# Sensor_module.net
KiCad netlist of a schematic drawn in Altium Designer
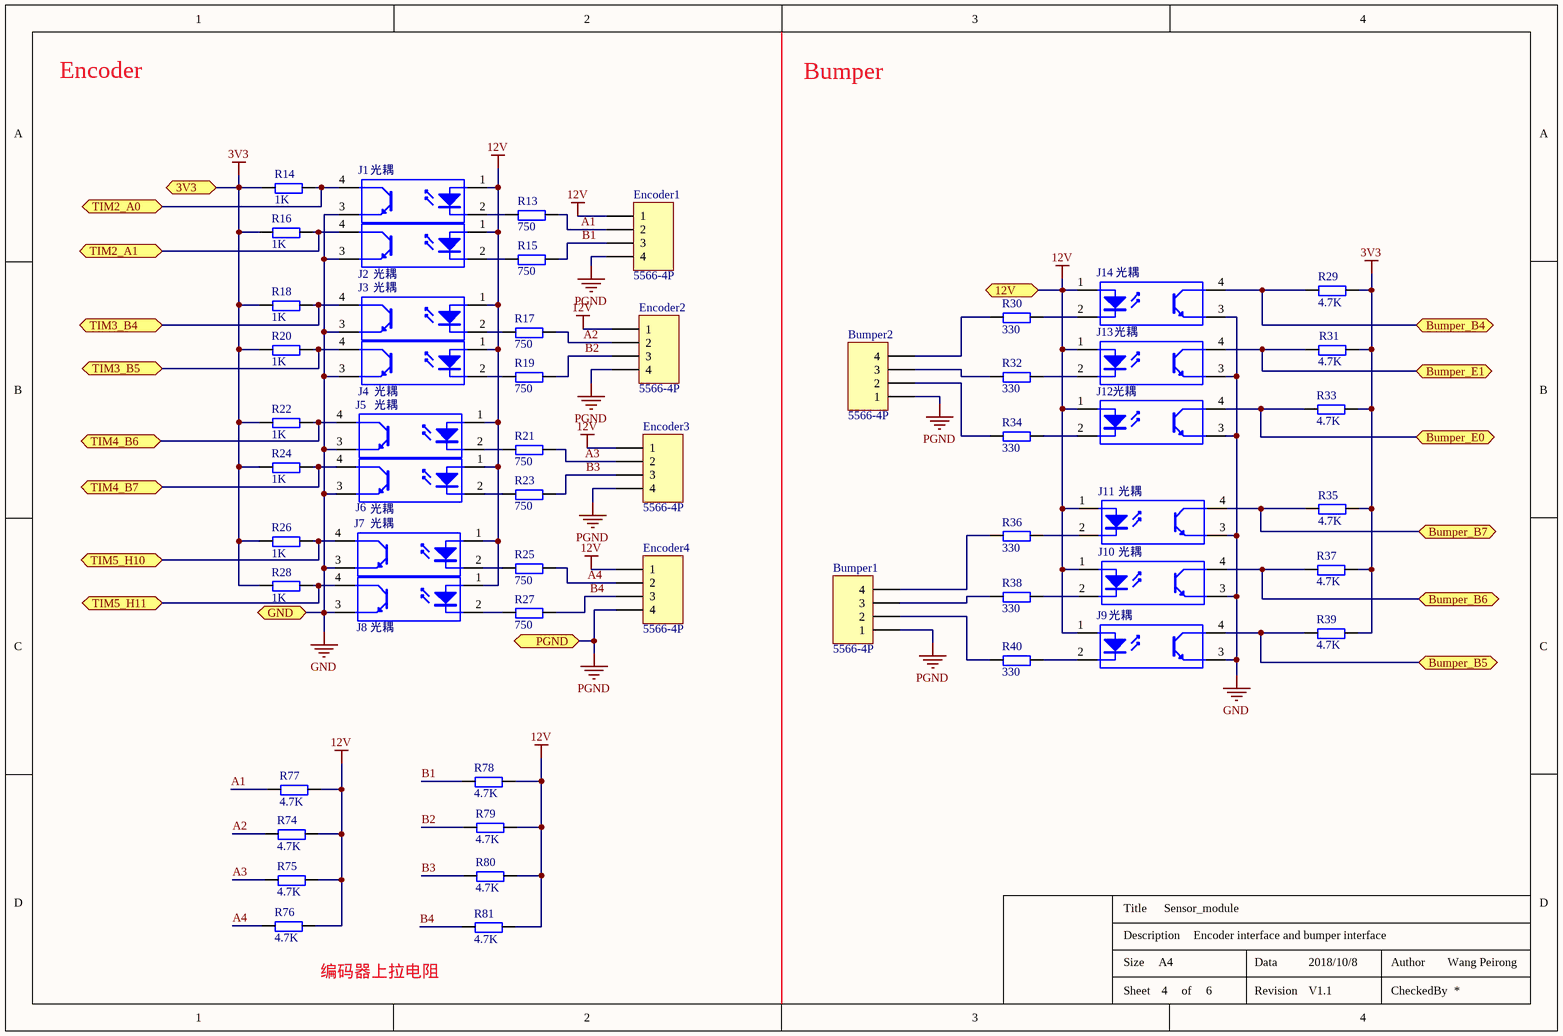
[diagram p0: Sensor_module.SchDoc]

(export (version "E")
  (design (tool "Eeschema 10.0.6"))
  (components
    (comp (ref "Bumper1")
      (value "5566-4P")
      (footprint "5566-4P")
      (description "Header, 4-Pin")
      (fields (field (name "PUBLISHER") "Altium Limited"))
      (libsource (lib "") (part "Header 4_1"))
    )
    (comp (ref "Bumper2")
      (value "5566-4P")
      (footprint "5566-4P")
      (description "Header, 4-Pin")
      (fields (field (name "PUBLISHER") "Altium Limited"))
      (libsource (lib "") (part "Header 4_1"))
    )
    (comp (ref "Encoder1")
      (value "5566-4P")
      (footprint "5566-4P")
      (description "Header, 4-Pin")
      (fields (field (name "PUBLISHER") "Altium Limited"))
      (libsource (lib "接插件集成库") (part "Header 4"))
    )
    (comp (ref "Encoder2")
      (value "5566-4P")
      (footprint "5566-4P")
      (description "Header, 4-Pin")
      (fields (field (name "PUBLISHER") "Altium Limited"))
      (libsource (lib "接插件集成库") (part "Header 4"))
    )
    (comp (ref "Encoder3")
      (value "5566-4P")
      (footprint "5566-4P")
      (description "Header, 4-Pin")
      (fields (field (name "PUBLISHER") "Altium Limited"))
      (libsource (lib "接插件集成库") (part "Header 4"))
    )
    (comp (ref "Encoder4")
      (value "5566-4P")
      (footprint "5566-4P")
      (description "Header, 4-Pin")
      (fields (field (name "PUBLISHER") "Altium Limited"))
      (libsource (lib "接插件集成库") (part "Header 4"))
    )
    (comp (ref "J1")
      (value "光耦")
      (footprint "SOP127P710X350-4N")
      (fields (field (name "PUBLISHER") "Altium Limited"))
      (libsource (lib "常用元件集成库") (part "光耦"))
    )
    (comp (ref "J2")
      (value "光耦")
      (footprint "SOP127P710X350-4N")
      (fields (field (name "PUBLISHER") "Altium Limited"))
      (libsource (lib "常用元件集成库") (part "光耦"))
    )
    (comp (ref "J3")
      (value "光耦")
      (footprint "SOP127P710X350-4N")
      (fields (field (name "PUBLISHER") "Altium Limited"))
      (libsource (lib "常用元件集成库") (part "光耦"))
    )
    (comp (ref "J4")
      (value "光耦")
      (footprint "SOP127P710X350-4N")
      (fields (field (name "PUBLISHER") "Altium Limited"))
      (libsource (lib "常用元件集成库") (part "光耦"))
    )
    (comp (ref "J5")
      (value "光耦")
      (footprint "SOP127P710X350-4N")
      (fields (field (name "PUBLISHER") "Altium Limited"))
      (libsource (lib "常用元件集成库") (part "光耦"))
    )
    (comp (ref "J6")
      (value "光耦")
      (footprint "SOP127P710X350-4N")
      (fields (field (name "PUBLISHER") "Altium Limited"))
      (libsource (lib "常用元件集成库") (part "光耦"))
    )
    (comp (ref "J7")
      (value "光耦")
      (footprint "SOP127P710X350-4N")
      (fields (field (name "PUBLISHER") "Altium Limited"))
      (libsource (lib "常用元件集成库") (part "光耦"))
    )
    (comp (ref "J8")
      (value "光耦")
      (footprint "SOP127P710X350-4N")
      (fields (field (name "PUBLISHER") "Altium Limited"))
      (libsource (lib "常用元件集成库") (part "光耦"))
    )
    (comp (ref "J9")
      (value "光耦")
      (footprint "SOP127P710X350-4N")
      (fields (field (name "PUBLISHER") "Altium Limited"))
      (libsource (lib "常用元件集成库") (part "光耦"))
    )
    (comp (ref "J10")
      (value "光耦")
      (footprint "SOP127P710X350-4N")
      (fields (field (name "PUBLISHER") "Altium Limited"))
      (libsource (lib "常用元件集成库") (part "光耦"))
    )
    (comp (ref "J11")
      (value "光耦")
      (footprint "SOP127P710X350-4N")
      (fields (field (name "PUBLISHER") "Altium Limited"))
      (libsource (lib "常用元件集成库") (part "光耦"))
    )
    (comp (ref "J12")
      (value "光耦")
      (footprint "SOP127P710X350-4N")
      (fields (field (name "PUBLISHER") "Altium Limited"))
      (libsource (lib "常用元件集成库") (part "光耦"))
    )
    (comp (ref "J13")
      (value "光耦")
      (footprint "SOP127P710X350-4N")
      (fields (field (name "PUBLISHER") "Altium Limited"))
      (libsource (lib "常用元件集成库") (part "光耦"))
    )
    (comp (ref "J14")
      (value "光耦")
      (footprint "SOP127P710X350-4N")
      (fields (field (name "PUBLISHER") "Altium Limited"))
      (libsource (lib "常用元件集成库") (part "光耦"))
    )
    (comp (ref "R13") (value "750") (footprint "0603P") (libsource (lib "STM32F429核心板封装库") (part "R")))
    (comp (ref "R14") (value "1K") (footprint "0603P") (libsource (lib "STM32F429核心板封装库") (part "R")))
    (comp (ref "R15") (value "750") (footprint "0603P") (libsource (lib "阿波罗STM32F4&F7底板封装库") (part "R")))
    (comp (ref "R16") (value "1K") (footprint "0603P") (libsource (lib "阿波罗STM32F4&F7底板封装库") (part "R")))
    (comp (ref "R17") (value "750") (footprint "0603P") (libsource (lib "阿波罗STM32F4&F7底板封装库") (part "R")))
    (comp (ref "R18") (value "1K") (footprint "0603P") (libsource (lib "阿波罗STM32F4&F7底板封装库") (part "R")))
    (comp (ref "R19") (value "750") (footprint "0603P") (libsource (lib "阿波罗STM32F4&F7底板封装库") (part "R")))
    (comp (ref "R20") (value "1K") (footprint "0603P") (libsource (lib "阿波罗STM32F4&F7底板封装库") (part "R")))
    (comp (ref "R21") (value "750") (footprint "0603P") (libsource (lib "阿波罗STM32F4&F7底板封装库") (part "R")))
    (comp (ref "R22") (value "1K") (footprint "0603P") (libsource (lib "阿波罗STM32F4&F7底板封装库") (part "R")))
    (comp (ref "R23") (value "750") (footprint "0603P") (libsource (lib "阿波罗STM32F4&F7底板封装库") (part "R")))
    (comp (ref "R24") (value "1K") (footprint "0603P") (libsource (lib "阿波罗STM32F4&F7底板封装库") (part "R")))
    (comp (ref "R25") (value "750") (footprint "0603P") (libsource (lib "阿波罗STM32F4&F7底板封装库") (part "R")))
    (comp (ref "R26") (value "1K") (footprint "0603P") (libsource (lib "阿波罗STM32F4&F7底板封装库") (part "R")))
    (comp (ref "R27") (value "750") (footprint "0603P") (libsource (lib "阿波罗STM32F4&F7底板封装库") (part "R")))
    (comp (ref "R28") (value "1K") (footprint "0603P") (libsource (lib "阿波罗STM32F4&F7底板封装库") (part "R")))
    (comp (ref "R29") (value "4.7K") (footprint "0603P") (libsource (lib "阿波罗STM32F4&F7底板封装库") (part "R")))
    (comp (ref "R30") (value "330") (footprint "0603P") (libsource (lib "阿波罗STM32F4&F7底板封装库") (part "R")))
    (comp (ref "R31") (value "4.7K") (footprint "0603P") (libsource (lib "阿波罗STM32F4&F7底板封装库") (part "R")))
    (comp (ref "R32") (value "330") (footprint "0603P") (libsource (lib "阿波罗STM32F4&F7底板封装库") (part "R")))
    (comp (ref "R33") (value "4.7K") (footprint "0603P") (libsource (lib "阿波罗STM32F4&F7底板封装库") (part "R")))
    (comp (ref "R34") (value "330") (footprint "0603P") (libsource (lib "阿波罗STM32F4&F7底板封装库") (part "R")))
    (comp (ref "R35") (value "4.7K") (footprint "0603P") (libsource (lib "阿波罗STM32F4&F7底板封装库") (part "R")))
    (comp (ref "R36") (value "330") (footprint "0603P") (libsource (lib "阿波罗STM32F4&F7底板封装库") (part "R")))
    (comp (ref "R37") (value "4.7K") (footprint "0603P") (libsource (lib "阿波罗STM32F4&F7底板封装库") (part "R")))
    (comp (ref "R38") (value "330") (footprint "0603P") (libsource (lib "阿波罗STM32F4&F7底板封装库") (part "R")))
    (comp (ref "R39") (value "4.7K") (footprint "0603P") (libsource (lib "阿波罗STM32F4&F7底板封装库") (part "R")))
    (comp (ref "R40") (value "330") (footprint "0603P") (libsource (lib "阿波罗STM32F4&F7底板封装库") (part "R")))
    (comp (ref "R74") (value "4.7K") (footprint "0603P") (libsource (lib "阿波罗STM32F4&F7底板封装库") (part "R")))
    (comp (ref "R75") (value "4.7K") (footprint "0603P") (libsource (lib "阿波罗STM32F4&F7底板封装库") (part "R")))
    (comp (ref "R76") (value "4.7K") (footprint "0603P") (libsource (lib "阿波罗STM32F4&F7底板封装库") (part "R")))
    (comp (ref "R77") (value "4.7K") (footprint "0603P") (libsource (lib "阿波罗STM32F4&F7底板封装库") (part "R")))
    (comp (ref "R78") (value "4.7K") (footprint "0603P") (libsource (lib "阿波罗STM32F4&F7底板封装库") (part "R")))
    (comp (ref "R79") (value "4.7K") (footprint "0603P") (libsource (lib "阿波罗STM32F4&F7底板封装库") (part "R")))
    (comp (ref "R80") (value "4.7K") (footprint "0603P") (libsource (lib "阿波罗STM32F4&F7底板封装库") (part "R")))
    (comp (ref "R81") (value "4.7K") (footprint "0603P") (libsource (lib "阿波罗STM32F4&F7底板封装库") (part "R")))
  )
  (nets
    (net (code "1") (name "/A1") (class "Default")
      (node (ref "Encoder1") (pin "2") (pinfunction "2_2") (pintype "passive"))
      (node (ref "R13") (pin "1") (pintype "passive"))
      (node (ref "R77") (pin "1") (pintype "passive"))
    )
    (net (code "2") (name "/A2") (class "Default")
      (node (ref "Encoder2") (pin "2") (pinfunction "2_2") (pintype "passive"))
      (node (ref "R17") (pin "1") (pintype "passive"))
      (node (ref "R74") (pin "1") (pintype "passive"))
    )
    (net (code "3") (name "/A3") (class "Default")
      (node (ref "Encoder3") (pin "2") (pinfunction "2_2") (pintype "passive"))
      (node (ref "R21") (pin "1") (pintype "passive"))
      (node (ref "R75") (pin "1") (pintype "passive"))
    )
    (net (code "4") (name "/A4") (class "Default")
      (node (ref "Encoder4") (pin "2") (pinfunction "2_2") (pintype "passive"))
      (node (ref "R25") (pin "1") (pintype "passive"))
      (node (ref "R76") (pin "1") (pintype "passive"))
    )
    (net (code "5") (name "/B1") (class "Default")
      (node (ref "Encoder1") (pin "3") (pinfunction "3_3") (pintype "passive"))
      (node (ref "R15") (pin "1") (pintype "passive"))
      (node (ref "R78") (pin "1") (pintype "passive"))
    )
    (net (code "6") (name "/B2") (class "Default")
      (node (ref "Encoder2") (pin "3") (pinfunction "3_3") (pintype "passive"))
      (node (ref "R19") (pin "1") (pintype "passive"))
      (node (ref "R79") (pin "1") (pintype "passive"))
    )
    (net (code "7") (name "/B3") (class "Default")
      (node (ref "Encoder3") (pin "3") (pinfunction "3_3") (pintype "passive"))
      (node (ref "R23") (pin "1") (pintype "passive"))
      (node (ref "R80") (pin "1") (pintype "passive"))
    )
    (net (code "8") (name "/B4") (class "Default")
      (node (ref "Encoder4") (pin "3") (pinfunction "3_3") (pintype "passive"))
      (node (ref "R27") (pin "1") (pintype "passive"))
      (node (ref "R81") (pin "1") (pintype "passive"))
    )
    (net (code "9") (name "/Bumper_B4") (class "Default")
      (node (ref "J14") (pin "4") (pinfunction "C_4") (pintype "passive"))
      (node (ref "R29") (pin "1") (pintype "passive"))
    )
    (net (code "10") (name "/Bumper_B5") (class "Default")
      (node (ref "J9") (pin "4") (pinfunction "C_4") (pintype "passive"))
      (node (ref "R39") (pin "1") (pintype "passive"))
    )
    (net (code "11") (name "/Bumper_B6") (class "Default")
      (node (ref "J10") (pin "4") (pinfunction "C_4") (pintype "passive"))
      (node (ref "R37") (pin "1") (pintype "passive"))
    )
    (net (code "12") (name "/Bumper_B7") (class "Default")
      (node (ref "J11") (pin "4") (pinfunction "C_4") (pintype "passive"))
      (node (ref "R35") (pin "1") (pintype "passive"))
    )
    (net (code "13") (name "/Bumper_E0") (class "Default")
      (node (ref "J12") (pin "4") (pinfunction "C_4") (pintype "passive"))
      (node (ref "R33") (pin "1") (pintype "passive"))
    )
    (net (code "14") (name "/Bumper_E1") (class "Default")
      (node (ref "J13") (pin "4") (pinfunction "C_4") (pintype "passive"))
      (node (ref "R31") (pin "1") (pintype "passive"))
    )
    (net (code "15") (name "/TIM2_A0") (class "Default")
      (node (ref "J1") (pin "4") (pinfunction "C_4") (pintype "passive"))
      (node (ref "R14") (pin "1") (pintype "passive"))
    )
    (net (code "16") (name "/TIM2_A1") (class "Default")
      (node (ref "J2") (pin "4") (pinfunction "C_4") (pintype "passive"))
      (node (ref "R16") (pin "1") (pintype "passive"))
    )
    (net (code "17") (name "/TIM3_B4") (class "Default")
      (node (ref "J3") (pin "4") (pinfunction "C_4") (pintype "passive"))
      (node (ref "R18") (pin "1") (pintype "passive"))
    )
    (net (code "18") (name "/TIM3_B5") (class "Default")
      (node (ref "J4") (pin "4") (pinfunction "C_4") (pintype "passive"))
      (node (ref "R20") (pin "1") (pintype "passive"))
    )
    (net (code "19") (name "/TIM4_B6") (class "Default")
      (node (ref "J5") (pin "4") (pinfunction "C_4") (pintype "passive"))
      (node (ref "R22") (pin "1") (pintype "passive"))
    )
    (net (code "20") (name "/TIM4_B7") (class "Default")
      (node (ref "J6") (pin "4") (pinfunction "C_4") (pintype "passive"))
      (node (ref "R24") (pin "1") (pintype "passive"))
    )
    (net (code "21") (name "/TIM5_H10") (class "Default")
      (node (ref "J7") (pin "4") (pinfunction "C_4") (pintype "passive"))
      (node (ref "R26") (pin "1") (pintype "passive"))
    )
    (net (code "22") (name "/TIM5_H11") (class "Default")
      (node (ref "J8") (pin "4") (pinfunction "C_4") (pintype "passive"))
      (node (ref "R28") (pin "1") (pintype "passive"))
    )
    (net (code "23") (name "3V3") (class "Default")
      (node (ref "R14") (pin "2") (pintype "passive"))
      (node (ref "R16") (pin "2") (pintype "passive"))
      (node (ref "R18") (pin "2") (pintype "passive"))
      (node (ref "R20") (pin "2") (pintype "passive"))
      (node (ref "R22") (pin "2") (pintype "passive"))
      (node (ref "R24") (pin "2") (pintype "passive"))
      (node (ref "R26") (pin "2") (pintype "passive"))
      (node (ref "R28") (pin "2") (pintype "passive"))
      (node (ref "R29") (pin "2") (pintype "passive"))
      (node (ref "R31") (pin "2") (pintype "passive"))
      (node (ref "R33") (pin "2") (pintype "passive"))
      (node (ref "R35") (pin "2") (pintype "passive"))
      (node (ref "R37") (pin "2") (pintype "passive"))
      (node (ref "R39") (pin "2") (pintype "passive"))
    )
    (net (code "24") (name "12V") (class "Default")
      (node (ref "Encoder1") (pin "1") (pinfunction "1_1") (pintype "passive"))
      (node (ref "Encoder2") (pin "1") (pinfunction "1_1") (pintype "passive"))
      (node (ref "Encoder3") (pin "1") (pinfunction "1_1") (pintype "passive"))
      (node (ref "Encoder4") (pin "1") (pinfunction "1_1") (pintype "passive"))
      (node (ref "J1") (pin "1") (pinfunction "A_1") (pintype "passive"))
      (node (ref "J10") (pin "1") (pinfunction "A_1") (pintype "passive"))
      (node (ref "J11") (pin "1") (pinfunction "A_1") (pintype "passive"))
      (node (ref "J12") (pin "1") (pinfunction "A_1") (pintype "passive"))
      (node (ref "J13") (pin "1") (pinfunction "A_1") (pintype "passive"))
      (node (ref "J14") (pin "1") (pinfunction "A_1") (pintype "passive"))
      (node (ref "J2") (pin "1") (pinfunction "A_1") (pintype "passive"))
      (node (ref "J3") (pin "1") (pinfunction "A_1") (pintype "passive"))
      (node (ref "J4") (pin "1") (pinfunction "A_1") (pintype "passive"))
      (node (ref "J5") (pin "1") (pinfunction "A_1") (pintype "passive"))
      (node (ref "J6") (pin "1") (pinfunction "A_1") (pintype "passive"))
      (node (ref "J7") (pin "1") (pinfunction "A_1") (pintype "passive"))
      (node (ref "J8") (pin "1") (pinfunction "A_1") (pintype "passive"))
      (node (ref "J9") (pin "1") (pinfunction "A_1") (pintype "passive"))
      (node (ref "R74") (pin "2") (pintype "passive"))
      (node (ref "R75") (pin "2") (pintype "passive"))
      (node (ref "R76") (pin "2") (pintype "passive"))
      (node (ref "R77") (pin "2") (pintype "passive"))
      (node (ref "R78") (pin "2") (pintype "passive"))
      (node (ref "R79") (pin "2") (pintype "passive"))
      (node (ref "R80") (pin "2") (pintype "passive"))
      (node (ref "R81") (pin "2") (pintype "passive"))
    )
    (net (code "25") (name "GND") (class "Default")
      (node (ref "J1") (pin "3") (pinfunction "E_3") (pintype "passive"))
      (node (ref "J10") (pin "3") (pinfunction "E_3") (pintype "passive"))
      (node (ref "J11") (pin "3") (pinfunction "E_3") (pintype "passive"))
      (node (ref "J12") (pin "3") (pinfunction "E_3") (pintype "passive"))
      (node (ref "J13") (pin "3") (pinfunction "E_3") (pintype "passive"))
      (node (ref "J14") (pin "3") (pinfunction "E_3") (pintype "passive"))
      (node (ref "J2") (pin "3") (pinfunction "E_3") (pintype "passive"))
      (node (ref "J3") (pin "3") (pinfunction "E_3") (pintype "passive"))
      (node (ref "J4") (pin "3") (pinfunction "E_3") (pintype "passive"))
      (node (ref "J5") (pin "3") (pinfunction "E_3") (pintype "passive"))
      (node (ref "J6") (pin "3") (pinfunction "E_3") (pintype "passive"))
      (node (ref "J7") (pin "3") (pinfunction "E_3") (pintype "passive"))
      (node (ref "J8") (pin "3") (pinfunction "E_3") (pintype "passive"))
      (node (ref "J9") (pin "3") (pinfunction "E_3") (pintype "passive"))
    )
    (net (code "26") (name "Net-(Bumper1-Pad2)") (class "Default")
      (node (ref "Bumper1") (pin "2") (pinfunction "2_2") (pintype "passive"))
      (node (ref "R40") (pin "1") (pintype "passive"))
    )
    (net (code "27") (name "Net-(Bumper1-Pad3)") (class "Default")
      (node (ref "Bumper1") (pin "3") (pinfunction "3_3") (pintype "passive"))
      (node (ref "R38") (pin "1") (pintype "passive"))
    )
    (net (code "28") (name "Net-(Bumper1-Pad4)") (class "Default")
      (node (ref "Bumper1") (pin "4") (pinfunction "4_4") (pintype "passive"))
      (node (ref "R36") (pin "1") (pintype "passive"))
    )
    (net (code "29") (name "Net-(Bumper2-Pad2)") (class "Default")
      (node (ref "Bumper2") (pin "2") (pinfunction "2_2") (pintype "passive"))
      (node (ref "R34") (pin "1") (pintype "passive"))
    )
    (net (code "30") (name "Net-(Bumper2-Pad3)") (class "Default")
      (node (ref "Bumper2") (pin "3") (pinfunction "3_3") (pintype "passive"))
      (node (ref "R32") (pin "1") (pintype "passive"))
    )
    (net (code "31") (name "Net-(Bumper2-Pad4)") (class "Default")
      (node (ref "Bumper2") (pin "4") (pinfunction "4_4") (pintype "passive"))
      (node (ref "R30") (pin "1") (pintype "passive"))
    )
    (net (code "32") (name "Net-(J1-K)") (class "Default")
      (node (ref "J1") (pin "2") (pinfunction "K_2") (pintype "passive"))
      (node (ref "R13") (pin "2") (pintype "passive"))
    )
    (net (code "33") (name "Net-(J2-K)") (class "Default")
      (node (ref "J2") (pin "2") (pinfunction "K_2") (pintype "passive"))
      (node (ref "R15") (pin "2") (pintype "passive"))
    )
    (net (code "34") (name "Net-(J3-K)") (class "Default")
      (node (ref "J3") (pin "2") (pinfunction "K_2") (pintype "passive"))
      (node (ref "R17") (pin "2") (pintype "passive"))
    )
    (net (code "35") (name "Net-(J4-K)") (class "Default")
      (node (ref "J4") (pin "2") (pinfunction "K_2") (pintype "passive"))
      (node (ref "R19") (pin "2") (pintype "passive"))
    )
    (net (code "36") (name "Net-(J5-K)") (class "Default")
      (node (ref "J5") (pin "2") (pinfunction "K_2") (pintype "passive"))
      (node (ref "R21") (pin "2") (pintype "passive"))
    )
    (net (code "37") (name "Net-(J6-K)") (class "Default")
      (node (ref "J6") (pin "2") (pinfunction "K_2") (pintype "passive"))
      (node (ref "R23") (pin "2") (pintype "passive"))
    )
    (net (code "38") (name "Net-(J7-K)") (class "Default")
      (node (ref "J7") (pin "2") (pinfunction "K_2") (pintype "passive"))
      (node (ref "R25") (pin "2") (pintype "passive"))
    )
    (net (code "39") (name "Net-(J8-K)") (class "Default")
      (node (ref "J8") (pin "2") (pinfunction "K_2") (pintype "passive"))
      (node (ref "R27") (pin "2") (pintype "passive"))
    )
    (net (code "40") (name "Net-(J9-K)") (class "Default")
      (node (ref "J9") (pin "2") (pinfunction "K_2") (pintype "passive"))
      (node (ref "R40") (pin "2") (pintype "passive"))
    )
    (net (code "41") (name "Net-(J10-K)") (class "Default")
      (node (ref "J10") (pin "2") (pinfunction "K_2") (pintype "passive"))
      (node (ref "R38") (pin "2") (pintype "passive"))
    )
    (net (code "42") (name "Net-(J11-K)") (class "Default")
      (node (ref "J11") (pin "2") (pinfunction "K_2") (pintype "passive"))
      (node (ref "R36") (pin "2") (pintype "passive"))
    )
    (net (code "43") (name "Net-(J12-K)") (class "Default")
      (node (ref "J12") (pin "2") (pinfunction "K_2") (pintype "passive"))
      (node (ref "R34") (pin "2") (pintype "passive"))
    )
    (net (code "44") (name "Net-(J13-K)") (class "Default")
      (node (ref "J13") (pin "2") (pinfunction "K_2") (pintype "passive"))
      (node (ref "R32") (pin "2") (pintype "passive"))
    )
    (net (code "45") (name "Net-(J14-K)") (class "Default")
      (node (ref "J14") (pin "2") (pinfunction "K_2") (pintype "passive"))
      (node (ref "R30") (pin "2") (pintype "passive"))
    )
    (net (code "46") (name "PGND") (class "Default")
      (node (ref "Bumper1") (pin "1") (pinfunction "1_1") (pintype "passive"))
      (node (ref "Bumper2") (pin "1") (pinfunction "1_1") (pintype "passive"))
      (node (ref "Encoder1") (pin "4") (pinfunction "4_4") (pintype "passive"))
      (node (ref "Encoder2") (pin "4") (pinfunction "4_4") (pintype "passive"))
      (node (ref "Encoder3") (pin "4") (pinfunction "4_4") (pintype "passive"))
      (node (ref "Encoder4") (pin "4") (pinfunction "4_4") (pintype "passive"))
    )
  )
)
